# Sheet_Power.net
KiCad netlist of a schematic drawn in Altium Designer
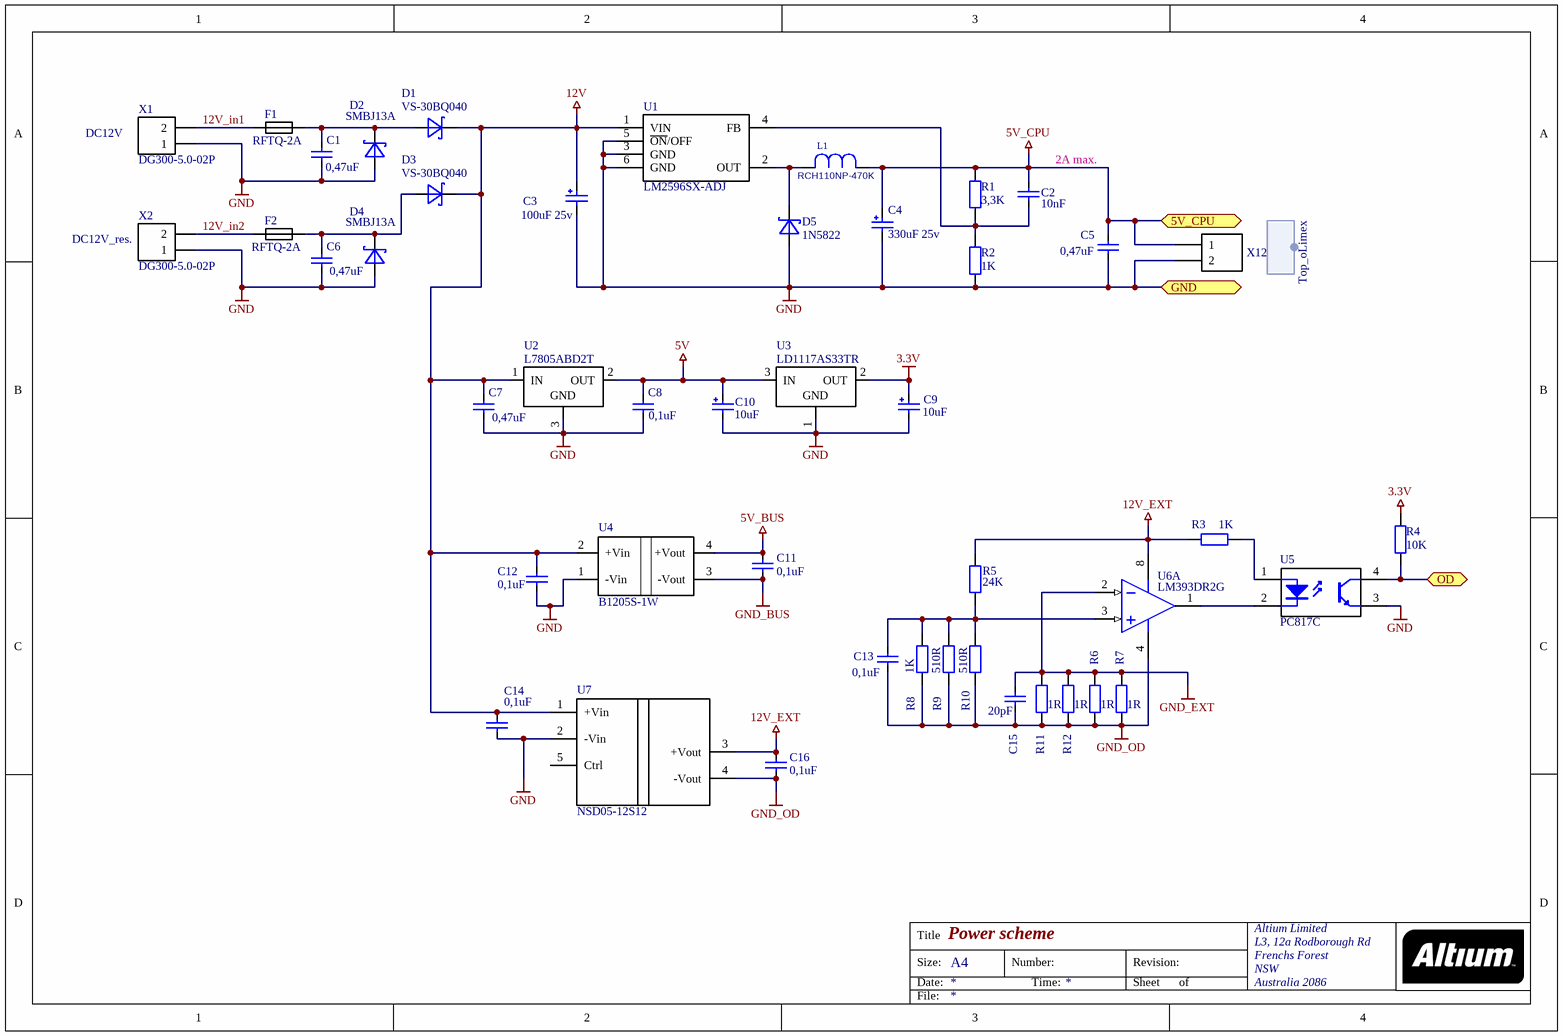
[diagram p0: Sheet_Power.SchDoc]

(export (version "E")
  (design (tool "Eeschema 10.0.6"))
  (components
    (comp (ref "C1")
      (value "0,47uF")
      (footprint "C_1206")
      (description "Capacitor semi")
      (fields (field (name "Comment") "Cap_Semi"))
      (libsource (lib "Capacitor") (part "Cap_Semi"))
    )
    (comp (ref "C2")
      (value "10nF")
      (footprint "C_0805")
      (description "Capacitor semi")
      (fields (field (name "Comment") "Cap_Semi"))
      (libsource (lib "Capacitor") (part "Cap_Semi"))
    )
    (comp (ref "C3")
      (value "100uF 25v")
      (footprint "8x11")
      (description "Capacitor Polar")
      (fields (field (name "Comment") "Cap_Polar"))
      (libsource (lib "Capacitor") (part "Cap_Polar"))
    )
    (comp (ref "C4")
      (value "330uF 25v")
      (footprint "10x16")
      (description "Capacitor Polar")
      (fields (field (name "Comment") "Cap_Polar"))
      (libsource (lib "Capacitor") (part "Cap_Polar"))
    )
    (comp (ref "C5")
      (value "0,47uF")
      (footprint "C_1206")
      (description "Capacitor semi")
      (fields (field (name "Comment") "Cap_Semi"))
      (libsource (lib "Capacitor") (part "Cap_Semi"))
    )
    (comp (ref "C6")
      (value "0,47uF")
      (footprint "C_1206")
      (description "Capacitor semi")
      (fields (field (name "Comment") "Cap_Semi"))
      (libsource (lib "Capacitor") (part "Cap_Semi"))
    )
    (comp (ref "C7")
      (value "0,47uF")
      (footprint "C_1206")
      (description "Capacitor semi")
      (fields (field (name "Comment") "Cap_Semi"))
      (libsource (lib "Capacitor") (part "Cap_Semi"))
    )
    (comp (ref "C8")
      (value "0,1uF")
      (footprint "C_0805")
      (description "Capacitor semi")
      (fields (field (name "Comment") "Cap_Semi"))
      (libsource (lib "Capacitor") (part "Cap_Semi"))
    )
    (comp (ref "C9")
      (value "10uF")
      (footprint "5x11")
      (description "Capacitor polar")
      (fields (field (name "Comment") "Cap_Polar"))
      (libsource (lib "Capacitor") (part "Capacitor Polar"))
    )
    (comp (ref "C10")
      (value "10uF")
      (footprint "5x11")
      (description "Capacitor polar")
      (fields (field (name "Comment") "Cap_Polar"))
      (libsource (lib "Capacitor") (part "Capacitor Polar"))
    )
    (comp (ref "C11")
      (value "0,1uF")
      (footprint "C_0805")
      (description "Capacitor semi")
      (fields (field (name "Comment") "Cap_Semi"))
      (libsource (lib "Capacitor") (part "Cap_Semi"))
    )
    (comp (ref "C12")
      (value "0,1uF")
      (footprint "C_0805")
      (description "Capacitor semi")
      (fields (field (name "Comment") "Cap_Semi"))
      (libsource (lib "Capacitor") (part "Cap_Semi"))
    )
    (comp (ref "C13")
      (value "0,1uF")
      (footprint "C_0805")
      (description "Capacitor semi")
      (fields (field (name "Comment") "Cap_Semi"))
      (libsource (lib "Capacitor") (part "Cap_Semi"))
    )
    (comp (ref "C14")
      (value "0,1uF")
      (footprint "C_0805")
      (description "Capacitor semi")
      (fields (field (name "Comment") "Cap_Semi"))
      (libsource (lib "Capacitor") (part "Cap_Semi"))
    )
    (comp (ref "C15")
      (value "20pF")
      (footprint "C_0805")
      (description "Capacitor semi")
      (fields (field (name "Comment") "Cap_Semi"))
      (libsource (lib "Capacitor") (part "Cap_Semi"))
    )
    (comp (ref "C16")
      (value "0,1uF")
      (footprint "C_0805")
      (description "Capacitor semi")
      (fields (field (name "Comment") "Cap_Semi"))
      (libsource (lib "Capacitor") (part "Cap_Semi"))
    )
    (comp (ref "D1")
      (value "VS-30BQ040")
      (footprint "SMC")
      (description "Diode Schottky")
      (libsource (lib "Diode") (part "VS-30BQ040"))
    )
    (comp (ref "D2")
      (value "SMBJ13A")
      (footprint "SMB")
      (description "Supressor")
      (libsource (lib "Diode") (part "SMBJ13A"))
    )
    (comp (ref "D3")
      (value "VS-30BQ040")
      (footprint "SMC")
      (description "Diode Schottky")
      (libsource (lib "Diode") (part "VS-30BQ040"))
    )
    (comp (ref "D4")
      (value "SMBJ13A")
      (footprint "SMB")
      (description "Supressor")
      (libsource (lib "Diode") (part "SMBJ13A"))
    )
    (comp (ref "D5")
      (value "1N5822")
      (footprint "DO-201")
      (description "Diode Schottky")
      (libsource (lib "Diode") (part "1N5822"))
    )
    (comp (ref "F1")
      (value "RFTQ-2A")
      (footprint "Fuse RFTQ")
      (description "Fuse")
      (libsource (lib "Other") (part "Fuse"))
    )
    (comp (ref "F2")
      (value "RFTQ-2A")
      (footprint "Fuse RFTQ")
      (description "Fuse")
      (libsource (lib "Other") (part "Fuse"))
    )
    (comp (ref "L1")
      (value "RCH110NP-470K")
      (footprint "RCH-110")
      (description "Inductor")
      (libsource (lib "Induction") (part "Inductor"))
    )
    (comp (ref "R1")
      (value "3,3K")
      (footprint "R_0805")
      (description "Resistor")
      (libsource (lib "Resistors") (part "Resistor"))
    )
    (comp (ref "R2")
      (value "1K")
      (footprint "R_0805")
      (description "Resistor")
      (libsource (lib "Resistors") (part "Resistor"))
    )
    (comp (ref "R3")
      (value "1K")
      (footprint "R_0805")
      (description "Resistor")
      (libsource (lib "") (part "Resistor_1"))
    )
    (comp (ref "R4")
      (value "10K")
      (footprint "R_0805")
      (description "Resistor")
      (libsource (lib "Resistors") (part "Resistor"))
    )
    (comp (ref "R5")
      (value "24K")
      (footprint "R_0805")
      (description "Resistor")
      (libsource (lib "Resistors") (part "Resistor"))
    )
    (comp (ref "R6")
      (value "1R")
      (footprint "R_1206")
      (description "Resistor")
      (libsource (lib "Resistors") (part "Resistor"))
    )
    (comp (ref "R7")
      (value "1R")
      (footprint "R_1206")
      (description "Resistor")
      (libsource (lib "Resistors") (part "Resistor"))
    )
    (comp (ref "R8")
      (value "1K")
      (footprint "R_0805")
      (description "Resistor")
      (libsource (lib "Resistors") (part "Resistor"))
    )
    (comp (ref "R9")
      (value "510R")
      (footprint "R_0805")
      (description "Resistor")
      (libsource (lib "Resistors") (part "Resistor"))
    )
    (comp (ref "R10")
      (value "510R")
      (footprint "R_0805")
      (description "Resistor")
      (libsource (lib "Resistors") (part "Resistor"))
    )
    (comp (ref "R11")
      (value "1R")
      (footprint "R_1206")
      (description "Resistor")
      (libsource (lib "Resistors") (part "Resistor"))
    )
    (comp (ref "R12")
      (value "1R")
      (footprint "R_1206")
      (description "Resistor")
      (libsource (lib "Resistors") (part "Resistor"))
    )
    (comp (ref "U1")
      (value "LM2596SX-ADJ")
      (footprint "D2PAK_5p")
      (description "Easy Switcher 3.0A Step-Down Voltage Regulator")
      (libsource (lib "Power") (part "LM2596SX-ADJ"))
    )
    (comp (ref "U2")
      (value "L7805ABD2T")
      (footprint "D2PAK_3p")
      (description "Voltage Regulators")
      (libsource (lib "Power") (part "L7805ABD2T"))
    )
    (comp (ref "U3")
      (value "LD1117AS33TR")
      (footprint "SOT-223_N")
      (description "Voltage Regulators 800mA")
      (libsource (lib "Power") (part "LD1117AS33TR"))
    )
    (comp (ref "U4")
      (value "B1205S-1W")
      (footprint "SIP4")
      (description "DC/DC converter")
      (libsource (lib "Power") (part "B0505S-1W"))
    )
    (comp (ref "U5")
      (value "PC817C")
      (footprint "DIP-4")
      (description "Optocoupler")
      (libsource (lib "Chip_Packaging") (part "PC817"))
    )
    (comp (ref "U6")
      (value "LM393DR2G")
      (footprint "SO-8_L")
      (description "Dual Comparators")
      (libsource (lib "Chip_Packaging") (part "LM393DR2G"))
    )
    (comp (ref "U7")
      (value "NSD05-12S12")
      (footprint "NSD05")
      (description "DC/DC Regulated Single Output")
      (libsource (lib "Power") (part "NSD05-12S12"))
    )
    (comp (ref "X1")
      (value "DG300-5.0-02P")
      (footprint "5mm 2")
      (description "Connector 5mm")
      (fields (field (name "ALTIUM_UNNAMED_1") "DG300-5.0-02P"))
      (libsource (lib "Connect") (part "DG300_2pin"))
    )
    (comp (ref "X2")
      (value "DG300-5.0-02P")
      (footprint "5mm 2")
      (description "Connector 5mm")
      (fields (field (name "ALTIUM_UNNAMED_1") "DG300-5.0-02P"))
      (libsource (lib "Connect") (part "DG300_2pin"))
    )
    (comp (ref "X12")
      (value "PLS-2")
      (footprint "PLS-2-3D")
      (description "Header, 2-Pin")
      (fields (field (name "PUBLISHER") "Altium Limited"))
      (libsource (lib "Connect") (part "PLS-2"))
    )
  )
  (nets
    (net (code "1") (name "/12V_in1") (class "Default")
      (node (ref "F1") (pin "2") (pintype "passive"))
      (node (ref "X1") (pin "2") (pinfunction "2_2") (pintype "passive"))
    )
    (net (code "2") (name "/12V_in2") (class "Default")
      (node (ref "F2") (pin "2") (pintype "passive"))
      (node (ref "X2") (pin "2") (pinfunction "2_2") (pintype "passive"))
    )
    (net (code "3") (name "/OD") (class "Default")
      (node (ref "R4") (pin "1") (pinfunction "1_1") (pintype "passive"))
      (node (ref "U5") (pin "4") (pinfunction "C_4") (pintype "passive"))
    )
    (net (code "4") (name "3.3V") (class "Default")
      (node (ref "C9") (pin "1") (pinfunction "1_1") (pintype "passive"))
      (node (ref "R4") (pin "2") (pinfunction "2_2") (pintype "passive"))
      (node (ref "U3") (pin "2") (pinfunction "OUT_2") (pintype "power_in"))
    )
    (net (code "5") (name "5V") (class "Default")
      (node (ref "C10") (pin "1") (pinfunction "1_1") (pintype "passive"))
      (node (ref "C8") (pin "2") (pinfunction "2_2") (pintype "passive"))
      (node (ref "U2") (pin "2") (pinfunction "OUT_2") (pintype "power_in"))
      (node (ref "U3") (pin "3") (pinfunction "IN_3") (pintype "power_in"))
    )
    (net (code "6") (name "5V_BUS") (class "Default")
      (node (ref "C11") (pin "1") (pinfunction "1_1") (pintype "passive"))
      (node (ref "U4") (pin "4") (pinfunction "+Vout_4") (pintype "power_in"))
    )
    (net (code "7") (name "5V_CPU") (class "Default")
      (node (ref "C2") (pin "1") (pinfunction "1_1") (pintype "passive"))
      (node (ref "C4") (pin "1") (pinfunction "1_1") (pintype "passive"))
      (node (ref "C5") (pin "2") (pinfunction "2_2") (pintype "passive"))
      (node (ref "L1") (pin "1") (pintype "passive"))
      (node (ref "R1") (pin "2") (pinfunction "2_2") (pintype "passive"))
      (node (ref "X12") (pin "1") (pinfunction "1_1") (pintype "passive"))
    )
    (net (code "8") (name "12V") (class "Default")
      (node (ref "C12") (pin "1") (pinfunction "1_1") (pintype "passive"))
      (node (ref "C14") (pin "2") (pinfunction "2_2") (pintype "passive"))
      (node (ref "C3") (pin "1") (pinfunction "1_1") (pintype "passive"))
      (node (ref "C7") (pin "2") (pinfunction "2_2") (pintype "passive"))
      (node (ref "D1") (pin "2") (pinfunction "C_2") (pintype "passive"))
      (node (ref "D3") (pin "2") (pinfunction "C_2") (pintype "passive"))
      (node (ref "U1") (pin "1") (pinfunction "VIN_1") (pintype "power_in"))
      (node (ref "U2") (pin "1") (pinfunction "IN_1") (pintype "power_in"))
      (node (ref "U4") (pin "2") (pinfunction "+Vin_2") (pintype "power_in"))
      (node (ref "U7") (pin "1") (pinfunction "+Vin_1") (pintype "power_in"))
    )
    (net (code "9") (name "12V_EXT") (class "Default")
      (node (ref "C16") (pin "2") (pinfunction "2_2") (pintype "passive"))
      (node (ref "R3") (pin "1") (pinfunction "1_1") (pintype "passive"))
      (node (ref "R5") (pin "2") (pinfunction "2_2") (pintype "passive"))
      (node (ref "U6") (pin "8") (pinfunction "VCC_8") (pintype "power_in"))
      (node (ref "U7") (pin "3") (pinfunction "+Vout_3") (pintype "power_in"))
    )
    (net (code "10") (name "GND") (class "Default")
      (node (ref "C1") (pin "1") (pinfunction "1_1") (pintype "passive"))
      (node (ref "C10") (pin "2") (pinfunction "2_2") (pintype "passive"))
      (node (ref "C12") (pin "2") (pinfunction "2_2") (pintype "passive"))
      (node (ref "C14") (pin "1") (pinfunction "1_1") (pintype "passive"))
      (node (ref "C3") (pin "2") (pinfunction "2_2") (pintype "passive"))
      (node (ref "C4") (pin "2") (pinfunction "2_2") (pintype "passive"))
      (node (ref "C5") (pin "1") (pinfunction "1_1") (pintype "passive"))
      (node (ref "C6") (pin "1") (pinfunction "1_1") (pintype "passive"))
      (node (ref "C7") (pin "1") (pinfunction "1_1") (pintype "passive"))
      (node (ref "C8") (pin "1") (pinfunction "1_1") (pintype "passive"))
      (node (ref "C9") (pin "2") (pinfunction "2_2") (pintype "passive"))
      (node (ref "D2") (pin "1") (pinfunction "A_1") (pintype "passive"))
      (node (ref "D4") (pin "1") (pinfunction "A_1") (pintype "passive"))
      (node (ref "D5") (pin "1") (pinfunction "A_1") (pintype "passive"))
      (node (ref "R2") (pin "1") (pinfunction "1_1") (pintype "passive"))
      (node (ref "U1") (pin "3") (pinfunction "GND_3") (pintype "power_in"))
      (node (ref "U1") (pin "5") (pinfunction "~{ON}/OFF_5") (pintype "passive"))
      (node (ref "U1") (pin "6") (pinfunction "GND_6") (pintype "power_in"))
      (node (ref "U2") (pin "3") (pinfunction "GND_3") (pintype "power_in"))
      (node (ref "U3") (pin "1") (pinfunction "GND_1") (pintype "power_in"))
      (node (ref "U4") (pin "1") (pinfunction "-Vin_1") (pintype "power_in"))
      (node (ref "U5") (pin "3") (pinfunction "E_3") (pintype "passive"))
      (node (ref "U7") (pin "2") (pinfunction "-Vin_2") (pintype "power_in"))
      (node (ref "X1") (pin "1") (pinfunction "1_1") (pintype "passive"))
      (node (ref "X12") (pin "2") (pinfunction "2_2") (pintype "passive"))
      (node (ref "X2") (pin "1") (pinfunction "1_1") (pintype "passive"))
    )
    (net (code "11") (name "GND_BUS") (class "Default")
      (node (ref "C11") (pin "2") (pinfunction "2_2") (pintype "passive"))
      (node (ref "U4") (pin "3") (pinfunction "-Vout_3") (pintype "power_in"))
    )
    (net (code "12") (name "GND_EXT") (class "Default")
      (node (ref "C15") (pin "2") (pinfunction "2_2") (pintype "passive"))
      (node (ref "R11") (pin "2") (pinfunction "2_2") (pintype "passive"))
      (node (ref "R12") (pin "2") (pinfunction "2_2") (pintype "passive"))
      (node (ref "R6") (pin "2") (pinfunction "2_2") (pintype "passive"))
      (node (ref "R7") (pin "2") (pinfunction "2_2") (pintype "passive"))
      (node (ref "U6") (pin "2") (pinfunction "INA-_2") (pintype "input"))
    )
    (net (code "13") (name "GND_OD") (class "Default")
      (node (ref "C13") (pin "1") (pinfunction "1_1") (pintype "passive"))
      (node (ref "C15") (pin "1") (pinfunction "1_1") (pintype "passive"))
      (node (ref "C16") (pin "1") (pinfunction "1_1") (pintype "passive"))
      (node (ref "R10") (pin "1") (pinfunction "1_1") (pintype "passive"))
      (node (ref "R11") (pin "1") (pinfunction "1_1") (pintype "passive"))
      (node (ref "R12") (pin "1") (pinfunction "1_1") (pintype "passive"))
      (node (ref "R6") (pin "1") (pinfunction "1_1") (pintype "passive"))
      (node (ref "R7") (pin "1") (pinfunction "1_1") (pintype "passive"))
      (node (ref "R8") (pin "1") (pinfunction "1_1") (pintype "passive"))
      (node (ref "R9") (pin "1") (pinfunction "1_1") (pintype "passive"))
      (node (ref "U6") (pin "4") (pinfunction "GND_4") (pintype "power_in"))
      (node (ref "U7") (pin "4") (pinfunction "-Vout_4") (pintype "power_in"))
    )
    (net (code "14") (name "Net-(D1-A)") (class "Default")
      (node (ref "C1") (pin "2") (pinfunction "2_2") (pintype "passive"))
      (node (ref "D1") (pin "1") (pinfunction "A_1") (pintype "passive"))
      (node (ref "D2") (pin "2") (pinfunction "C_2") (pintype "passive"))
      (node (ref "F1") (pin "1") (pintype "passive"))
    )
    (net (code "15") (name "Net-(D3-A)") (class "Default")
      (node (ref "C6") (pin "2") (pinfunction "2_2") (pintype "passive"))
      (node (ref "D3") (pin "1") (pinfunction "A_1") (pintype "passive"))
      (node (ref "D4") (pin "2") (pinfunction "C_2") (pintype "passive"))
      (node (ref "F2") (pin "1") (pintype "passive"))
    )
    (net (code "16") (name "Net-(D5-C)") (class "Default")
      (node (ref "D5") (pin "2") (pinfunction "C_2") (pintype "passive"))
      (node (ref "L1") (pin "2") (pintype "passive"))
      (node (ref "U1") (pin "2") (pinfunction "OUT_2") (pintype "open_emitter"))
    )
    (net (code "17") (name "Net-(U1-FB)") (class "Default")
      (node (ref "C2") (pin "2") (pinfunction "2_2") (pintype "passive"))
      (node (ref "R1") (pin "1") (pinfunction "1_1") (pintype "passive"))
      (node (ref "R2") (pin "2") (pinfunction "2_2") (pintype "passive"))
      (node (ref "U1") (pin "4") (pinfunction "FB_4") (pintype "passive"))
    )
    (net (code "18") (name "Net-(U5-A)") (class "Default")
      (node (ref "R3") (pin "2") (pinfunction "2_2") (pintype "passive"))
      (node (ref "U5") (pin "1") (pinfunction "A_1") (pintype "passive"))
    )
    (net (code "19") (name "Net-(U5-K)") (class "Default")
      (node (ref "U5") (pin "2") (pinfunction "K_2") (pintype "passive"))
      (node (ref "U6") (pin "1") (pinfunction "OUTA_1") (pintype "open_collector"))
    )
    (net (code "20") (name "Net-(U6A-INA+)") (class "Default")
      (node (ref "C13") (pin "2") (pinfunction "2_2") (pintype "passive"))
      (node (ref "R10") (pin "2") (pinfunction "2_2") (pintype "passive"))
      (node (ref "R5") (pin "1") (pinfunction "1_1") (pintype "passive"))
      (node (ref "R8") (pin "2") (pinfunction "2_2") (pintype "passive"))
      (node (ref "R9") (pin "2") (pinfunction "2_2") (pintype "passive"))
      (node (ref "U6") (pin "3") (pinfunction "INA+_3") (pintype "input"))
    )
    (net (code "21") (name "unconnected-(U7-Ctrl-Pad5)") (class "Default")
      (node (ref "U7") (pin "5") (pinfunction "Ctrl_5") (pintype "passive"))
    )
  )
)
